# socket_2bridges.net
KiCad netlist of a schematic drawn in Altium Designer
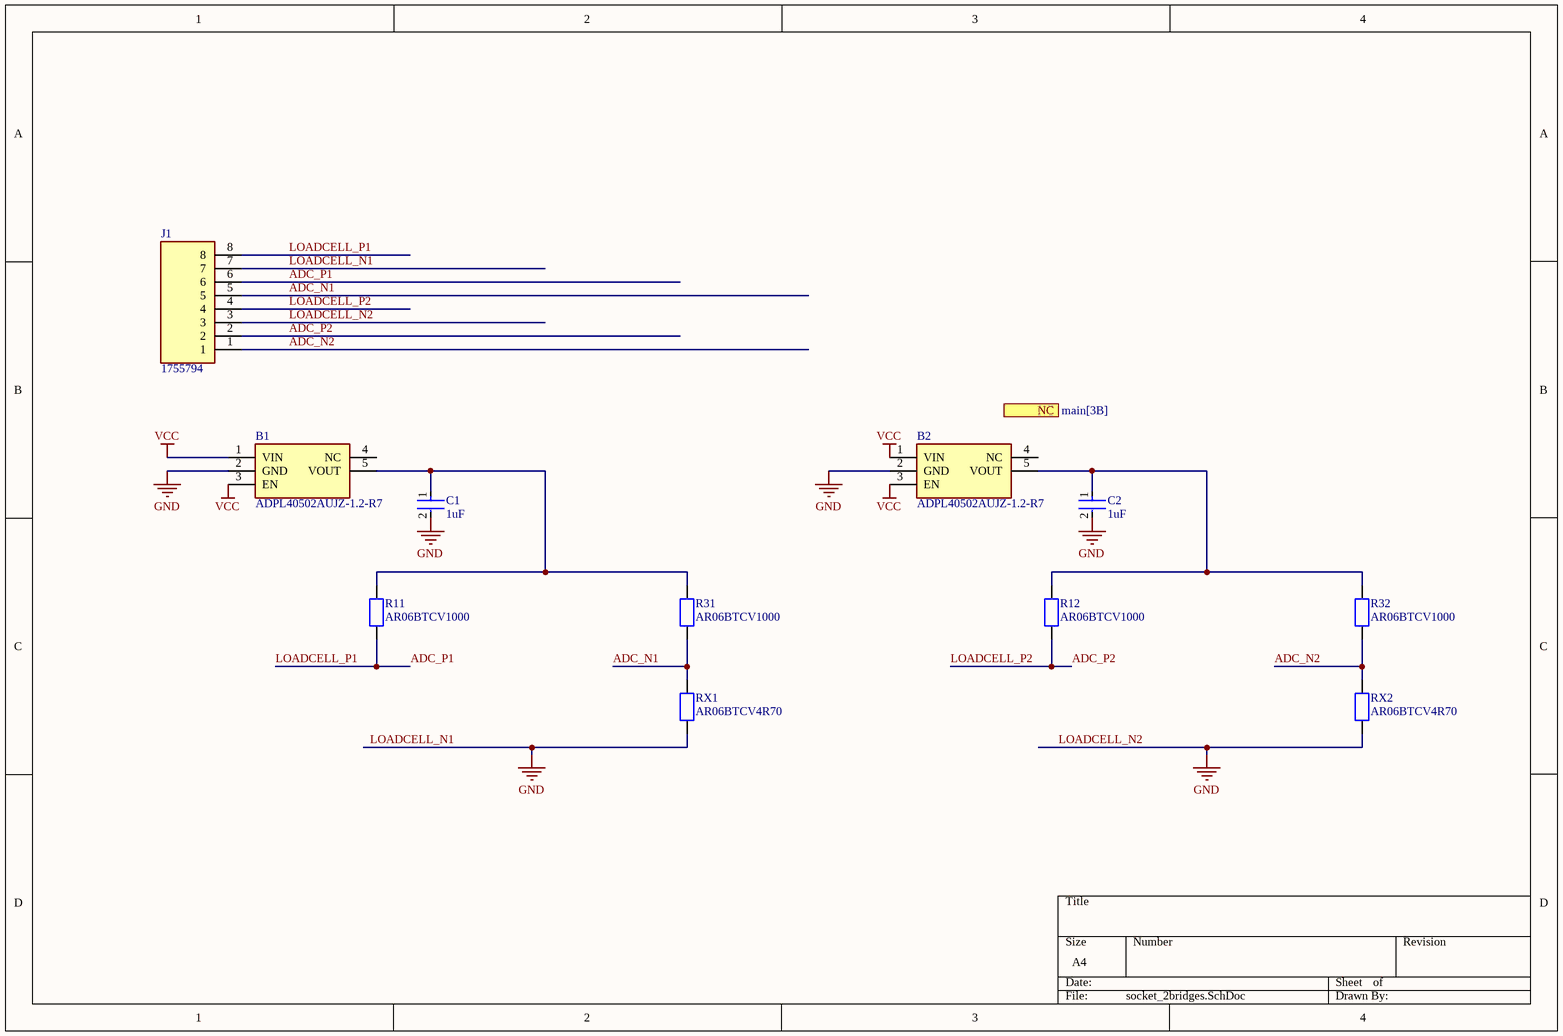
[diagram p0: socket_2bridges.SchDoc]

(export (version "E")
  (design (tool "Eeschema 10.0.6"))
  (components
    (comp (ref "B1")
      (value "ADPL40502AUJZ-1.2-R7")
      (footprint "SOT95P280X100-5N")
      (description "Low Noise, 200mA, CMOS Linear Regulator")
      (libsource (lib "ADPL40502AUJZ-1.2-R7") (part "ADPL40502AUJZ-1.2-R7"))
    )
    (comp (ref "B2")
      (value "ADPL40502AUJZ-1.2-R7")
      (footprint "SOT95P280X100-5N")
      (description "Low Noise, 200mA, CMOS Linear Regulator")
      (libsource (lib "ADPL40502AUJZ-1.2-R7") (part "ADPL40502AUJZ-1.2-R7"))
    )
    (comp (ref "C1")
      (value "1uF")
      (footprint "FP-CGA5L-0_3-0_1-IPC_A")
      (description "Cap Ceramic 1uF 25V X7R 10% Pad SMD 1206 +125°C Automotive T/R")
      (fields (field (name "TOLERANCE") "10%"))
      (libsource (lib "Altium Content Vault") (part "b4654b650e69147ec39a6b967a45e02"))
    )
    (comp (ref "C2")
      (value "1uF")
      (footprint "FP-CGA5L-0_3-0_1-IPC_A")
      (description "Cap Ceramic 1uF 25V X7R 10% Pad SMD 1206 +125°C Automotive T/R")
      (fields (field (name "TOLERANCE") "10%"))
      (libsource (lib "Altium Content Vault") (part "b4654b650e69147ec39a6b967a45e02"))
    )
    (comp (ref "J1")
      (value "1755794")
      (footprint "1755794:1755794")
      (description "Connector")
      (fields (field (name "MOUSER PART NUMBER") "651-1755794"))
      (libsource (lib "1755794") (part "1755794"))
    )
    (comp (ref "R11")
      (value "AR06BTCV1000")
      (footprint "AR06")
      (libsource (lib "AR06") (part "AR06BTCV1000"))
    )
    (comp (ref "R12")
      (value "AR06BTCV1000")
      (footprint "AR06")
      (libsource (lib "AR06") (part "AR06BTCV1000"))
    )
    (comp (ref "R31")
      (value "AR06BTCV1000")
      (footprint "AR06")
      (libsource (lib "AR06") (part "AR06BTCV1000"))
    )
    (comp (ref "R32")
      (value "AR06BTCV1000")
      (footprint "AR06")
      (libsource (lib "AR06") (part "AR06BTCV1000"))
    )
    (comp (ref "RX1")
      (value "AR06BTCV4R70")
      (footprint "AR06")
      (libsource (lib "AR06") (part "AR06BTCV4R70"))
    )
    (comp (ref "RX2")
      (value "AR06BTCV4R70")
      (footprint "AR06")
      (libsource (lib "AR06") (part "AR06BTCV4R70"))
    )
  )
  (nets
    (net (code "1") (name "/ADC_N1") (class "Default")
      (node (ref "J1") (pin "5") (pinfunction "5_5") (pintype "passive"))
      (node (ref "R31") (pin "1") (pinfunction "1_1") (pintype "passive"))
      (node (ref "RX1") (pin "2") (pinfunction "2_2") (pintype "passive"))
    )
    (net (code "2") (name "/ADC_N2") (class "Default")
      (node (ref "J1") (pin "1") (pinfunction "1_1") (pintype "passive"))
      (node (ref "R32") (pin "1") (pinfunction "1_1") (pintype "passive"))
      (node (ref "RX2") (pin "2") (pinfunction "2_2") (pintype "passive"))
    )
    (net (code "3") (name "/ADC_P1") (class "Default")
      (node (ref "J1") (pin "6") (pinfunction "6_6") (pintype "passive"))
      (node (ref "J1") (pin "8") (pinfunction "8_8") (pintype "passive"))
      (node (ref "R11") (pin "1") (pinfunction "1_1") (pintype "passive"))
    )
    (net (code "4") (name "/ADC_P2") (class "Default")
      (node (ref "J1") (pin "2") (pinfunction "2_2") (pintype "passive"))
      (node (ref "J1") (pin "4") (pinfunction "4_4") (pintype "passive"))
      (node (ref "R12") (pin "1") (pinfunction "1_1") (pintype "passive"))
    )
    (net (code "6") (name "GND") (class "Default")
      (node (ref "B1") (pin "2") (pinfunction "GND_2") (pintype "passive"))
      (node (ref "B2") (pin "2") (pinfunction "GND_2") (pintype "passive"))
      (node (ref "C1") (pin "2") (pinfunction "2_2") (pintype "passive"))
      (node (ref "C2") (pin "2") (pinfunction "2_2") (pintype "passive"))
      (node (ref "J1") (pin "3") (pinfunction "3_3") (pintype "passive"))
      (node (ref "J1") (pin "7") (pinfunction "7_7") (pintype "passive"))
      (node (ref "RX1") (pin "1") (pinfunction "1_1") (pintype "passive"))
      (node (ref "RX2") (pin "1") (pinfunction "1_1") (pintype "passive"))
    )
    (net (code "7") (name "Net-(B1-VOUT)") (class "Default")
      (node (ref "B1") (pin "5") (pinfunction "VOUT_5") (pintype "passive"))
      (node (ref "C1") (pin "1") (pinfunction "1_1") (pintype "passive"))
      (node (ref "R11") (pin "2") (pinfunction "2_2") (pintype "passive"))
      (node (ref "R31") (pin "2") (pinfunction "2_2") (pintype "passive"))
    )
    (net (code "8") (name "Net-(B2-VOUT)") (class "Default")
      (node (ref "B2") (pin "5") (pinfunction "VOUT_5") (pintype "passive"))
      (node (ref "C2") (pin "1") (pinfunction "1_1") (pintype "passive"))
      (node (ref "R12") (pin "2") (pinfunction "2_2") (pintype "passive"))
      (node (ref "R32") (pin "2") (pinfunction "2_2") (pintype "passive"))
    )
    (net (code "9") (name "VCC") (class "Default")
      (node (ref "B1") (pin "1") (pinfunction "VIN_1") (pintype "passive"))
      (node (ref "B1") (pin "3") (pinfunction "EN_3") (pintype "passive"))
      (node (ref "B2") (pin "1") (pinfunction "VIN_1") (pintype "passive"))
      (node (ref "B2") (pin "3") (pinfunction "EN_3") (pintype "passive"))
    )
    (net (code "10") (name "unconnected-(B1-NC-Pad4)") (class "Default")
      (node (ref "B1") (pin "4") (pinfunction "NC_4") (pintype "passive"))
    )
    (net (code "11") (name "unconnected-(B2-NC-Pad4)") (class "Default")
      (node (ref "B2") (pin "4") (pinfunction "NC_4") (pintype "passive"))
    )
  )
)
